# Peripherals.net
KiCad netlist of a schematic drawn in Altium Designer
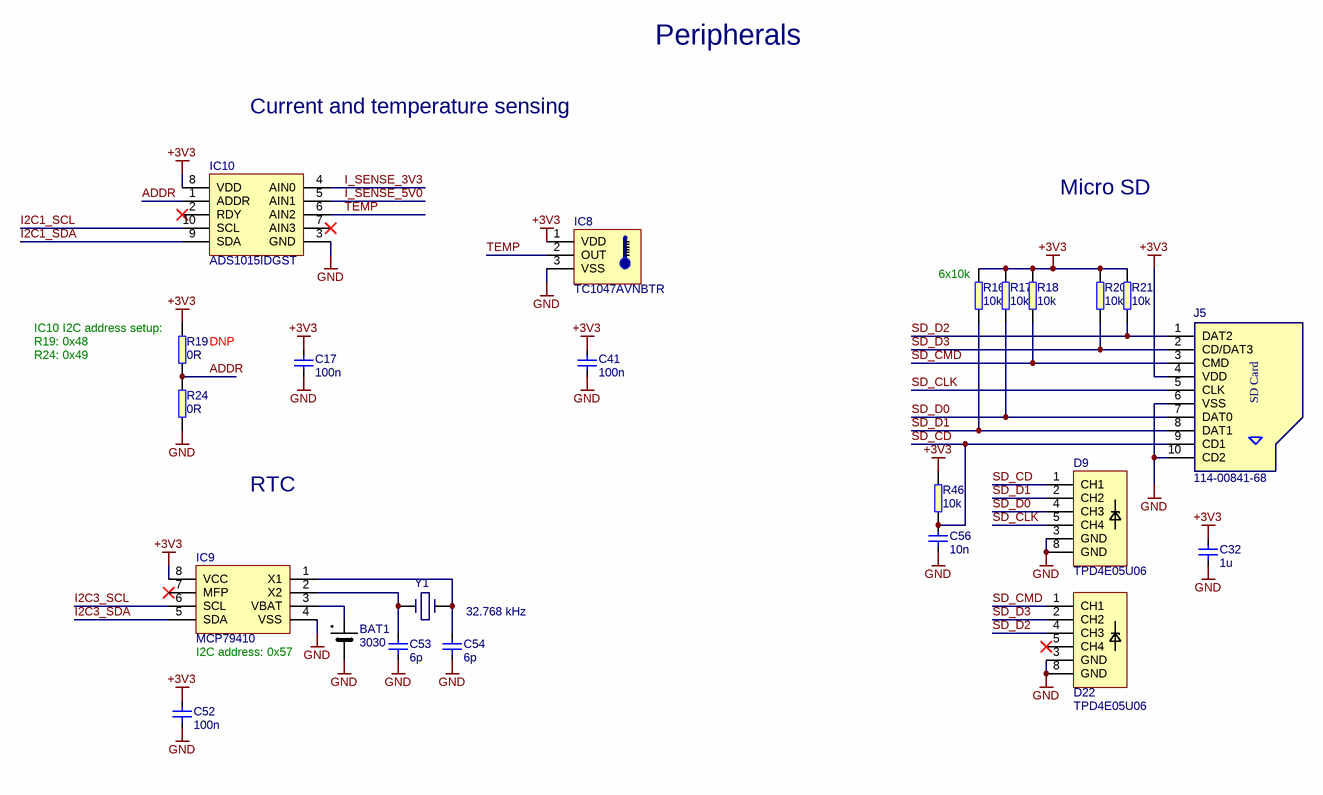
[diagram p0: Peripherals.SchDoc]

(export (version "E")
  (design (tool "Eeschema 10.0.6"))
  (components
    (comp (ref "BAT1")
      (value "3030")
      (footprint "KEYSTONE_CR1025")
      (description "SMT holder for  CR1025 battery")
      (fields (field (name "PART NUMBER") "Keystone_CR1025") (field (name "MANUFACTURER") "Keystone"))
      (libsource (lib "TK1Baseboard") (part "battery"))
    )
    (comp (ref "C17")
      (value "100n")
      (footprint "0402")
      (description "MLCC SMT Capacitor 100n 0402")
      (fields (field (name "MANUFACTURER") "TDK") (field (name "PART NUMBER") "C_100n_0402"))
      (libsource (lib "TK1Baseboard") (part "C_100n_0402"))
    )
    (comp (ref "C32")
      (value "1u")
      (footprint "0402")
      (description "MLCC SMT Capacitor 1uF 0402")
      (fields (field (name "MANUFACTURER") "MULTICOMP") (field (name "PART NUMBER") "C_1u_0402"))
      (libsource (lib "TK1Baseboard") (part "C_1u_0402"))
    )
    (comp (ref "C41")
      (value "100n")
      (footprint "0402")
      (description "MLCC SMT Capacitor 100n 0402")
      (fields (field (name "MANUFACTURER") "TDK") (field (name "PART NUMBER") "C_100n_0402"))
      (libsource (lib "TK1Baseboard") (part "C_100n_0402"))
    )
    (comp (ref "C52")
      (value "100n")
      (footprint "0402")
      (description "MLCC SMT Capacitor 100n 0402")
      (fields (field (name "MANUFACTURER") "TDK") (field (name "PART NUMBER") "C_100n_0402"))
      (libsource (lib "TK1Baseboard") (part "C_100n_0402"))
    )
    (comp (ref "C53")
      (value "6p")
      (footprint "0402")
      (description "MLCC SMT Capacitor 6pF 0402")
      (fields (field (name "MANUFACTURER") "WALSIN") (field (name "PART NUMBER") "C_6p_0402"))
      (libsource (lib "TK1Baseboard") (part "C_6p_0402"))
    )
    (comp (ref "C54")
      (value "6p")
      (footprint "0402")
      (description "MLCC SMT Capacitor 6pF 0402")
      (fields (field (name "MANUFACTURER") "WALSIN") (field (name "PART NUMBER") "C_6p_0402"))
      (libsource (lib "TK1Baseboard") (part "C_6p_0402"))
    )
    (comp (ref "C56")
      (value "10n")
      (footprint "0402")
      (description "MLCC SMT Capacitor 10 nF 0402")
      (fields (field (name "MANUFACTURER") "AVX") (field (name "PART NUMBER") "C_10n_0402"))
      (libsource (lib "TK1Baseboard") (part "C_10n_0402"))
    )
    (comp (ref "D9")
      (value "TPD4E05U06")
      (footprint "TPD4E05U06_PASS")
      (description "ESD Suppressors 4-CH")
      (fields
        (field (name "PART NUMBER") "TPD4E05U06_PASS")
        (field (name "MANUFACTURER") "Texas Instruments")
      )
      (libsource (lib "TK1Baseboard") (part "TPD4E05U06_PASS"))
    )
    (comp (ref "D22")
      (value "TPD4E05U06")
      (footprint "TPD4E05U06_PASS")
      (description "ESD Suppressors 4-CH")
      (fields
        (field (name "PART NUMBER") "TPD4E05U06_PASS")
        (field (name "MANUFACTURER") "Texas Instruments")
      )
      (libsource (lib "TK1Baseboard") (part "TPD4E05U06_PASS"))
    )
    (comp (ref "IC8")
      (value "TC1047AVNBTR")
      (footprint "SOT-23")
      (description "Precision Temperature-to-Voltage Converter")
      (fields (field (name "PART NUMBER") "TC1047A") (field (name "MANUFACTURER") "MICROCHIP"))
      (libsource (lib "TK1Baseboard") (part "TC1047A"))
    )
    (comp (ref "IC9")
      (value "MCP79410")
      (footprint "SOIC-8")
      (description "RTC timer with EEPROM and I2C interface")
      (fields (field (name "MANUFACTURER") "MICROCHIP") (field (name "MPN") "MCP79410-I/SN"))
      (libsource (lib "TK1Baseboard") (part "MCP79410"))
    )
    (comp (ref "IC10")
      (value "ADS1015IDGST")
      (footprint "MSOP10")
      (description "ADC 12BIT 4CH I2C")
      (fields (field (name "MANUFACTURER") "TEXAS INSTRUMENTS"))
      (libsource (lib "TK1Baseboard") (part "ADS1015"))
    )
    (comp (ref "J5")
      (value "114-00841-68")
      (footprint "114-00841-68")
      (description "Micro SD card holder")
      (fields
        (field (name "PART NUMBER") "AMP-114-00841-68")
        (field (name "MANUFACTURER") "AMPHENOL COMMERCIAL PRODUCTS")
      )
      (libsource (lib "TK1Baseboard") (part "Micro_SD"))
    )
    (comp (ref "R16")
      (value "10k")
      (footprint "0402")
      (description "RES, 10k, 0402")
      (fields (field (name "MANUFACTURER") "MULTICOMP") (field (name "PART NUMBER") "R_10k_0402"))
      (libsource (lib "TK1Baseboard") (part "R_10k_0402"))
    )
    (comp (ref "R17")
      (value "10k")
      (footprint "0402")
      (description "RES, 10k, 0402")
      (fields (field (name "MANUFACTURER") "MULTICOMP") (field (name "PART NUMBER") "R_10k_0402"))
      (libsource (lib "TK1Baseboard") (part "R_10k_0402"))
    )
    (comp (ref "R18")
      (value "10k")
      (footprint "0402")
      (description "RES, 10k, 0402")
      (fields (field (name "MANUFACTURER") "MULTICOMP") (field (name "PART NUMBER") "R_10k_0402"))
      (libsource (lib "TK1Baseboard") (part "R_10k_0402"))
    )
    (comp (ref "R19")
      (value "0R")
      (footprint "0603")
      (description "RES, 0R, 0603")
      (fields (field (name "MANUFACTURER") "BOURNS") (field (name "PART NUMBER") "R_0R_0603"))
      (libsource (lib "TK1Baseboard") (part "R_0R_0603"))
    )
    (comp (ref "R20")
      (value "10k")
      (footprint "0402")
      (description "RES, 10k, 0402")
      (fields (field (name "MANUFACTURER") "MULTICOMP") (field (name "PART NUMBER") "R_10k_0402"))
      (libsource (lib "TK1Baseboard") (part "R_10k_0402"))
    )
    (comp (ref "R21")
      (value "10k")
      (footprint "0402")
      (description "RES, 10k, 0402")
      (fields (field (name "MANUFACTURER") "MULTICOMP") (field (name "PART NUMBER") "R_10k_0402"))
      (libsource (lib "TK1Baseboard") (part "R_10k_0402"))
    )
    (comp (ref "R24")
      (value "0R")
      (footprint "0603")
      (description "RES, 0R, 0603")
      (fields (field (name "MANUFACTURER") "BOURNS") (field (name "PART NUMBER") "R_0R_0603"))
      (libsource (lib "TK1Baseboard") (part "R_0R_0603"))
    )
    (comp (ref "R46")
      (value "10k")
      (footprint "0402")
      (description "RES, 10k, 0402")
      (fields (field (name "MANUFACTURER") "MULTICOMP") (field (name "PART NUMBER") "R_10k_0402"))
      (libsource (lib "TK1Baseboard") (part "R_10k_0402"))
    )
    (comp (ref "Y1")
      (value "32.768 kHz")
      (footprint "ABS25")
      (description "CRYSTAL, 32.768KHz, 6PF, SMD")
      (fields (field (name "PART NUMBER") "ABS25-32.768KHZ-6-T") (field (name "MANUFACTURER") "ABRACON"))
      (libsource (lib "TK1Baseboard") (part "ABS25-32.768KHZ-6-T"))
    )
  )
  (nets
    (net (code "1") (name "+3V3") (class "Default")
      (node (ref "C17") (pin "1") (pinfunction "1_1") (pintype "passive"))
      (node (ref "C32") (pin "2") (pinfunction "2_2") (pintype "passive"))
      (node (ref "C41") (pin "1") (pinfunction "1_1") (pintype "passive"))
      (node (ref "C52") (pin "2") (pinfunction "2_2") (pintype "passive"))
      (node (ref "IC10") (pin "8") (pinfunction "VDD_8") (pintype "passive"))
      (node (ref "IC8") (pin "1") (pinfunction "VDD_1") (pintype "passive"))
      (node (ref "IC9") (pin "8") (pinfunction "VCC_8") (pintype "passive"))
      (node (ref "J5") (pin "4") (pinfunction "VDD_4") (pintype "passive"))
      (node (ref "R16") (pin "2") (pintype "passive"))
      (node (ref "R17") (pin "2") (pintype "passive"))
      (node (ref "R18") (pin "2") (pintype "passive"))
      (node (ref "R19") (pin "2") (pintype "passive"))
      (node (ref "R20") (pin "2") (pintype "passive"))
      (node (ref "R21") (pin "2") (pintype "passive"))
      (node (ref "R46") (pin "2") (pintype "passive"))
    )
    (net (code "2") (name "/ADDR") (class "Default")
      (node (ref "IC10") (pin "1") (pinfunction "ADDR_1") (pintype "passive"))
      (node (ref "R19") (pin "1") (pintype "passive"))
      (node (ref "R24") (pin "2") (pintype "passive"))
    )
    (net (code "3") (name "/I2C1_SCL") (class "Default")
      (node (ref "IC10") (pin "10") (pinfunction "SCL_10") (pintype "passive"))
    )
    (net (code "4") (name "/I2C1_SDA") (class "Default")
      (node (ref "IC10") (pin "9") (pinfunction "SDA_9") (pintype "passive"))
    )
    (net (code "5") (name "/I2C3_SCL") (class "Default")
      (node (ref "IC9") (pin "6") (pinfunction "SCL_6") (pintype "passive"))
    )
    (net (code "6") (name "/I2C3_SDA") (class "Default")
      (node (ref "IC9") (pin "5") (pinfunction "SDA_5") (pintype "passive"))
    )
    (net (code "7") (name "/I_SENSE_3V3") (class "Default")
      (node (ref "IC10") (pin "4") (pinfunction "AIN0_4") (pintype "passive"))
    )
    (net (code "8") (name "/I_SENSE_5V0") (class "Default")
      (node (ref "IC10") (pin "5") (pinfunction "AIN1_5") (pintype "passive"))
    )
    (net (code "9") (name "/SD_CD") (class "Default")
      (node (ref "C56") (pin "2") (pinfunction "2_2") (pintype "passive"))
      (node (ref "D9") (pin "1") (pinfunction "CH1_1") (pintype "passive"))
      (node (ref "J5") (pin "9") (pinfunction "CD1_9") (pintype "passive"))
      (node (ref "R46") (pin "1") (pintype "passive"))
    )
    (net (code "10") (name "/SD_CLK") (class "Default")
      (node (ref "D9") (pin "5") (pinfunction "CH4_5") (pintype "passive"))
      (node (ref "J5") (pin "5") (pinfunction "CLK_5") (pintype "passive"))
    )
    (net (code "11") (name "/SD_CMD") (class "Default")
      (node (ref "D22") (pin "1") (pinfunction "CH1_1") (pintype "passive"))
      (node (ref "J5") (pin "3") (pinfunction "CMD_3") (pintype "passive"))
      (node (ref "R18") (pin "1") (pintype "passive"))
    )
    (net (code "12") (name "/SD_D0") (class "Default")
      (node (ref "D9") (pin "4") (pinfunction "CH3_4") (pintype "passive"))
      (node (ref "J5") (pin "7") (pinfunction "DAT0_7") (pintype "passive"))
      (node (ref "R17") (pin "1") (pintype "passive"))
    )
    (net (code "13") (name "/SD_D1") (class "Default")
      (node (ref "D9") (pin "2") (pinfunction "CH2_2") (pintype "passive"))
      (node (ref "J5") (pin "8") (pinfunction "DAT1_8") (pintype "passive"))
      (node (ref "R16") (pin "1") (pintype "passive"))
    )
    (net (code "14") (name "/SD_D2") (class "Default")
      (node (ref "D22") (pin "4") (pinfunction "CH3_4") (pintype "passive"))
      (node (ref "J5") (pin "1") (pinfunction "DAT2_1") (pintype "passive"))
      (node (ref "R21") (pin "1") (pintype "passive"))
    )
    (net (code "15") (name "/SD_D3") (class "Default")
      (node (ref "D22") (pin "2") (pinfunction "CH2_2") (pintype "passive"))
      (node (ref "J5") (pin "2") (pinfunction "CD/DAT3_2") (pintype "passive"))
      (node (ref "R20") (pin "1") (pintype "passive"))
    )
    (net (code "16") (name "/TEMP") (class "Default")
      (node (ref "IC10") (pin "6") (pinfunction "AIN2_6") (pintype "passive"))
      (node (ref "IC8") (pin "2") (pinfunction "OUT_2") (pintype "passive"))
    )
    (net (code "17") (name "GND") (class "Default")
      (node (ref "BAT1") (pin "-") (pinfunction "-_-") (pintype "passive"))
      (node (ref "C17") (pin "2") (pinfunction "2_2") (pintype "passive"))
      (node (ref "C32") (pin "1") (pinfunction "1_1") (pintype "passive"))
      (node (ref "C41") (pin "2") (pinfunction "2_2") (pintype "passive"))
      (node (ref "C52") (pin "1") (pinfunction "1_1") (pintype "passive"))
      (node (ref "C53") (pin "1") (pinfunction "1_1") (pintype "passive"))
      (node (ref "C54") (pin "1") (pinfunction "1_1") (pintype "passive"))
      (node (ref "C56") (pin "1") (pinfunction "1_1") (pintype "passive"))
      (node (ref "D22") (pin "3") (pinfunction "GND_3") (pintype "passive"))
      (node (ref "D22") (pin "8") (pinfunction "GND_8") (pintype "passive"))
      (node (ref "D9") (pin "3") (pinfunction "GND_3") (pintype "passive"))
      (node (ref "D9") (pin "8") (pinfunction "GND_8") (pintype "passive"))
      (node (ref "IC10") (pin "3") (pinfunction "GND_3") (pintype "passive"))
      (node (ref "IC8") (pin "3") (pinfunction "VSS_3") (pintype "passive"))
      (node (ref "IC9") (pin "4") (pinfunction "VSS_4") (pintype "passive"))
      (node (ref "J5") (pin "10") (pinfunction "CD2_10") (pintype "passive"))
      (node (ref "J5") (pin "6") (pinfunction "VSS_6") (pintype "passive"))
      (node (ref "R24") (pin "1") (pintype "passive"))
    )
    (net (code "18") (name "Net-(IC9-VBAT)") (class "Default")
      (node (ref "BAT1") (pin "+") (pinfunction "+_+") (pintype "passive"))
      (node (ref "IC9") (pin "3") (pinfunction "VBAT_3") (pintype "passive"))
    )
    (net (code "19") (name "Net-(IC9-X1)") (class "Default")
      (node (ref "C54") (pin "2") (pinfunction "2_2") (pintype "passive"))
      (node (ref "IC9") (pin "1") (pinfunction "X1_1") (pintype "passive"))
      (node (ref "Y1") (pin "1") (pinfunction "1_1") (pintype "passive"))
    )
    (net (code "20") (name "Net-(IC9-X2)") (class "Default")
      (node (ref "C53") (pin "2") (pinfunction "2_2") (pintype "passive"))
      (node (ref "IC9") (pin "2") (pinfunction "X2_2") (pintype "passive"))
      (node (ref "Y1") (pin "2") (pinfunction "2_2") (pintype "passive"))
    )
    (net (code "21") (name "unconnected-(D22-CH4-Pad5)") (class "Default")
      (node (ref "D22") (pin "5") (pinfunction "CH4_5") (pintype "passive+no_connect"))
    )
    (net (code "22") (name "unconnected-(IC9-MFP-Pad7)") (class "Default")
      (node (ref "IC9") (pin "7") (pinfunction "MFP_7") (pintype "passive+no_connect"))
    )
    (net (code "23") (name "unconnected-(IC10-AIN3-Pad7)") (class "Default")
      (node (ref "IC10") (pin "7") (pinfunction "AIN3_7") (pintype "passive+no_connect"))
    )
    (net (code "24") (name "unconnected-(IC10-RDY-Pad2)") (class "Default")
      (node (ref "IC10") (pin "2") (pinfunction "RDY_2") (pintype "passive+no_connect"))
    )
  )
)
